# Monostable_Multivibrator.net
KiCad netlist of a schematic drawn in EAGLE
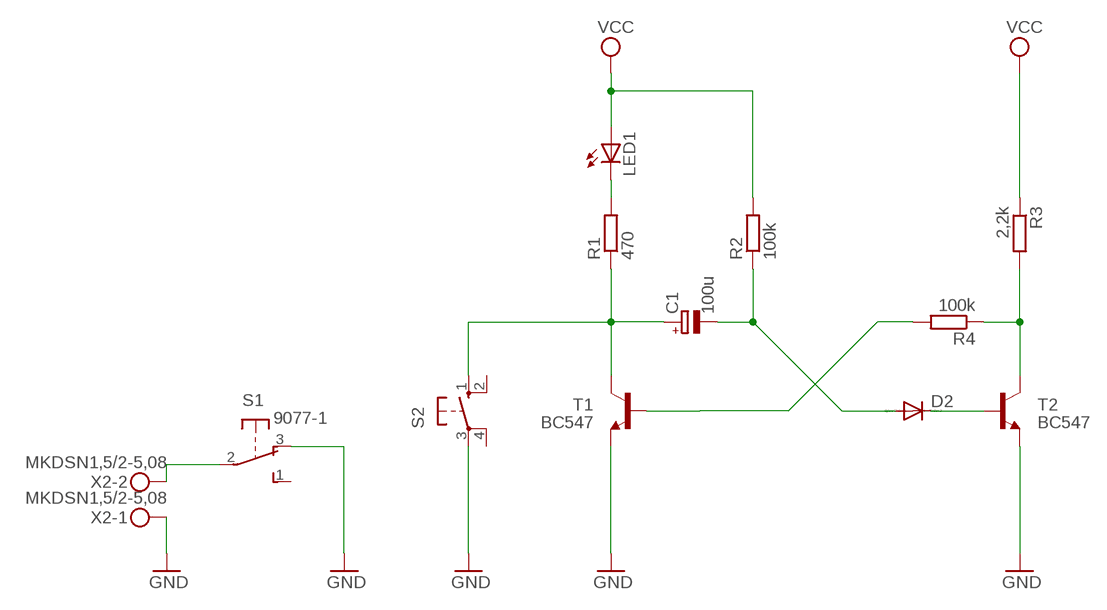
[diagram p0: schematic, sheet 1]

(export (version "E")
  (design (tool "Eeschema 10.0.6"))
  (components
    (comp (ref "C1")
      (value "100u")
      (footprint "eagle-import:E2,5-6")
      (libsource (lib "eagle-import") (part "CPOL-EUE2.5-6"))
    )
    (comp (ref "D2")
      (value "1N4148DO35-7")
      (footprint "eagle-import:DO35-7")
      (libsource (lib "eagle-import") (part "1N4148DO35-7"))
    )
    (comp (ref "LED1")
      (value "LED5MM")
      (footprint "eagle-import:LED5MM")
      (libsource (lib "eagle-import") (part "LED5MM"))
    )
    (comp (ref "R1")
      (value "470")
      (footprint "eagle-import:0207_10")
      (libsource (lib "eagle-import") (part "R-EU_0207/10"))
    )
    (comp (ref "R2")
      (value "100k")
      (footprint "eagle-import:0207_10")
      (libsource (lib "eagle-import") (part "R-EU_0207/10"))
    )
    (comp (ref "R3")
      (value "2,2k")
      (footprint "eagle-import:0207_10")
      (libsource (lib "eagle-import") (part "R-EU_0207/10"))
    )
    (comp (ref "R4")
      (value "100k")
      (footprint "eagle-import:0207_10")
      (libsource (lib "eagle-import") (part "R-EU_0207/10"))
    )
    (comp (ref "S1")
      (value "9077-1")
      (footprint "eagle-import:9077-1")
      (libsource (lib "eagle-import") (part "9077-1"))
    )
    (comp (ref "S2")
      (value "10-XX")
      (footprint "eagle-import:B3F-10XX")
      (fields (field (name "MPN") "B3F-1000"))
      (libsource (lib "eagle-import") (part "10-XX"))
    )
    (comp (ref "T1")
      (value "BC547")
      (footprint "eagle-import:TO92")
      (libsource (lib "eagle-import") (part "BC547B"))
    )
    (comp (ref "T2")
      (value "BC547")
      (footprint "eagle-import:TO92")
      (libsource (lib "eagle-import") (part "BC547B"))
    )
    (comp (ref "X2")
      (value "MKDSN1,5/2-5,08")
      (footprint "eagle-import:MKDSN1,5_2-5,08")
      (libsource (lib "eagle-import") (part "MKDSN1,5/2-5,08"))
    )
  )
  (nets
    (net (code "1") (name "GND") (class "Default")
      (node (ref "S1") (pin "3") (pinfunction "O_3") (pintype "passive"))
      (node (ref "S2") (pin "3") (pinfunction "P_3") (pintype "passive"))
      (node (ref "T1") (pin "1") (pinfunction "E_1") (pintype "passive"))
      (node (ref "T2") (pin "1") (pinfunction "E_1") (pintype "passive"))
      (node (ref "X2") (pin "1") (pinfunction "KL_1") (pintype "passive"))
    )
    (net (code "2") (name "Net-(C1-Pad-)") (class "Default")
      (node (ref "C1") (pin "-") (pinfunction "-_-") (pintype "passive"))
      (node (ref "D2") (pin "A") (pinfunction "A_A") (pintype "passive"))
      (node (ref "R2") (pin "1") (pinfunction "1_1") (pintype "passive"))
    )
    (net (code "3") (name "Net-(LED1-C)") (class "Default")
      (node (ref "LED1") (pin "K") (pinfunction "C_K") (pintype "passive"))
      (node (ref "R1") (pin "2") (pinfunction "2_2") (pintype "passive"))
    )
    (net (code "4") (name "Net-(S1-P)") (class "Default")
      (node (ref "S1") (pin "2") (pinfunction "P_2") (pintype "passive"))
      (node (ref "X2") (pin "2") (pinfunction "KL_2") (pintype "passive"))
    )
    (net (code "5") (name "Net-(S2-S)") (class "Default")
      (node (ref "C1") (pin "+") (pinfunction "+_+") (pintype "passive"))
      (node (ref "R1") (pin "1") (pinfunction "1_1") (pintype "passive"))
      (node (ref "S2") (pin "1") (pinfunction "S_1") (pintype "passive"))
      (node (ref "T1") (pin "3") (pinfunction "C_3") (pintype "passive"))
    )
    (net (code "6") (name "Net-(T1-B)") (class "Default")
      (node (ref "R4") (pin "2") (pinfunction "2_2") (pintype "passive"))
      (node (ref "T1") (pin "2") (pinfunction "B_2") (pintype "passive"))
    )
    (net (code "7") (name "Net-(T2-B)") (class "Default")
      (node (ref "D2") (pin "C") (pinfunction "C_C") (pintype "passive"))
      (node (ref "T2") (pin "2") (pinfunction "B_2") (pintype "passive"))
    )
    (net (code "8") (name "Net-(T2-C)") (class "Default")
      (node (ref "R3") (pin "2") (pinfunction "2_2") (pintype "passive"))
      (node (ref "R4") (pin "1") (pinfunction "1_1") (pintype "passive"))
      (node (ref "T2") (pin "3") (pinfunction "C_3") (pintype "passive"))
    )
    (net (code "9") (name "VCC") (class "Default")
      (node (ref "LED1") (pin "A") (pinfunction "A_A") (pintype "passive"))
      (node (ref "R2") (pin "2") (pinfunction "2_2") (pintype "passive"))
      (node (ref "R3") (pin "1") (pinfunction "1_1") (pintype "passive"))
    )
    (net (code "10") (name "unconnected-(S1-S-Pad1)") (class "Default")
      (node (ref "S1") (pin "1") (pinfunction "S_1") (pintype "passive"))
    )
    (net (code "11") (name "unconnected-(S2-P1-Pad4)") (class "Default")
      (node (ref "S2") (pin "4") (pinfunction "P1_4") (pintype "passive"))
    )
    (net (code "12") (name "unconnected-(S2-S1-Pad2)") (class "Default")
      (node (ref "S2") (pin "2") (pinfunction "S1_2") (pintype "passive"))
    )
  )
)
